# thermocouple_v0_1.net
KiCad netlist of a schematic drawn in EAGLE
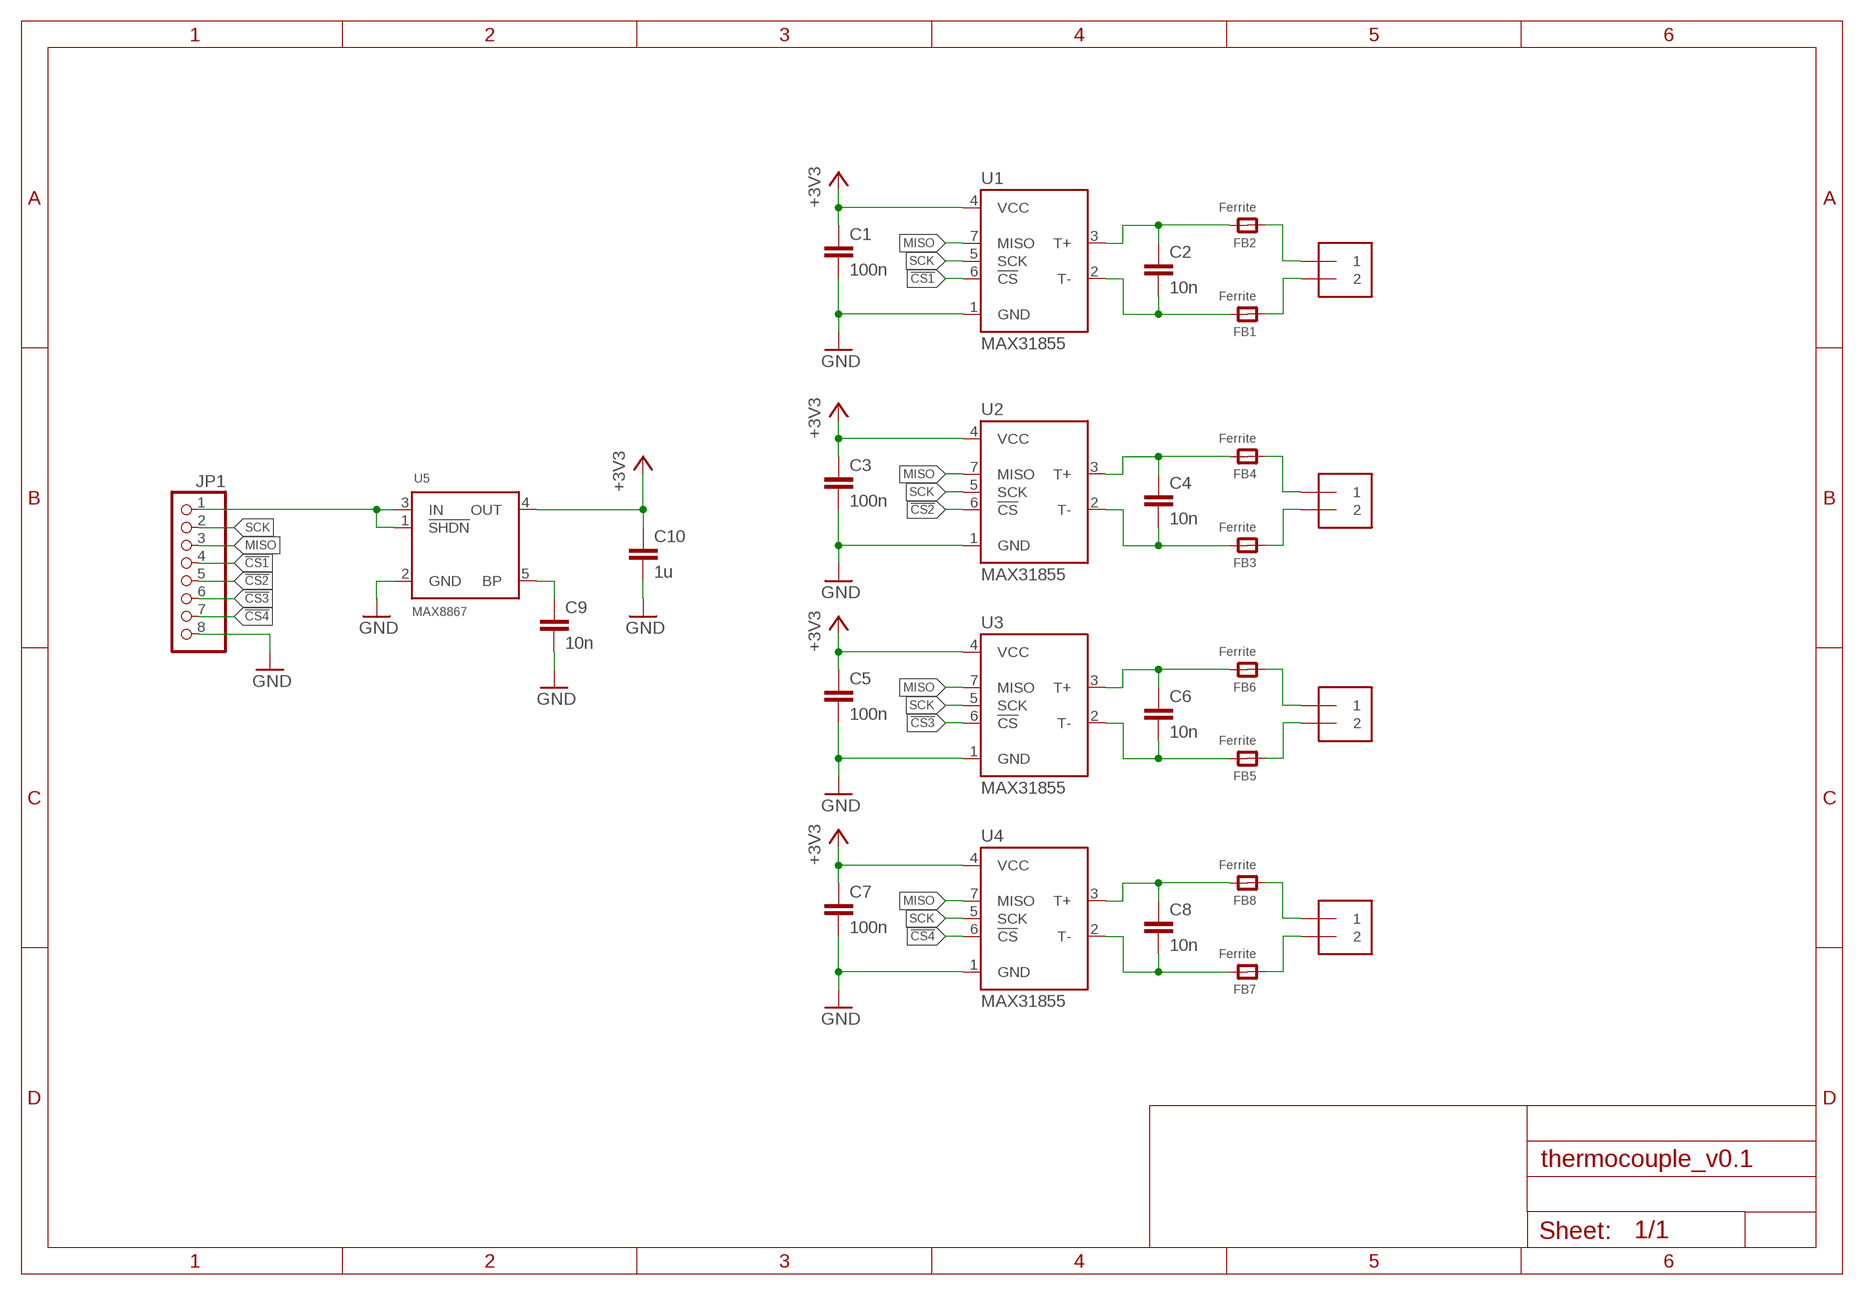
[diagram p0: schematic, sheet 1]

(export (version "E")
  (design (tool "Eeschema 10.0.6"))
  (components
    (comp (ref "C1")
      (value "100n")
      (footprint "eagle-import:C0603")
      (libsource (lib "eagle-import") (part "C-EUC0603"))
    )
    (comp (ref "C2")
      (value "10n")
      (footprint "eagle-import:C0603")
      (libsource (lib "eagle-import") (part "C-EUC0603"))
    )
    (comp (ref "C3")
      (value "100n")
      (footprint "eagle-import:C0603")
      (libsource (lib "eagle-import") (part "C-EUC0603"))
    )
    (comp (ref "C4")
      (value "10n")
      (footprint "eagle-import:C0603")
      (libsource (lib "eagle-import") (part "C-EUC0603"))
    )
    (comp (ref "C5")
      (value "100n")
      (footprint "eagle-import:C0603")
      (libsource (lib "eagle-import") (part "C-EUC0603"))
    )
    (comp (ref "C6")
      (value "10n")
      (footprint "eagle-import:C0603")
      (libsource (lib "eagle-import") (part "C-EUC0603"))
    )
    (comp (ref "C7")
      (value "100n")
      (footprint "eagle-import:C0603")
      (libsource (lib "eagle-import") (part "C-EUC0603"))
    )
    (comp (ref "C8")
      (value "10n")
      (footprint "eagle-import:C0603")
      (libsource (lib "eagle-import") (part "C-EUC0603"))
    )
    (comp (ref "C9")
      (value "10n")
      (footprint "eagle-import:C0603")
      (libsource (lib "eagle-import") (part "C-EUC0603"))
    )
    (comp (ref "C10")
      (value "1u")
      (footprint "eagle-import:C0603")
      (libsource (lib "eagle-import") (part "C-EUC0603"))
    )
    (comp (ref "FB1")
      (value "Ferrite")
      (footprint "eagle-import:_0805")
      (libsource (lib "eagle-import") (part "FERRITE_0805"))
    )
    (comp (ref "FB2")
      (value "Ferrite")
      (footprint "eagle-import:_0805")
      (libsource (lib "eagle-import") (part "FERRITE_0805"))
    )
    (comp (ref "FB3")
      (value "Ferrite")
      (footprint "eagle-import:_0805")
      (libsource (lib "eagle-import") (part "FERRITE_0805"))
    )
    (comp (ref "FB4")
      (value "Ferrite")
      (footprint "eagle-import:_0805")
      (libsource (lib "eagle-import") (part "FERRITE_0805"))
    )
    (comp (ref "FB5")
      (value "Ferrite")
      (footprint "eagle-import:_0805")
      (libsource (lib "eagle-import") (part "FERRITE_0805"))
    )
    (comp (ref "FB6")
      (value "Ferrite")
      (footprint "eagle-import:_0805")
      (libsource (lib "eagle-import") (part "FERRITE_0805"))
    )
    (comp (ref "FB7")
      (value "Ferrite")
      (footprint "eagle-import:_0805")
      (libsource (lib "eagle-import") (part "FERRITE_0805"))
    )
    (comp (ref "FB8")
      (value "Ferrite")
      (footprint "eagle-import:_0805")
      (libsource (lib "eagle-import") (part "FERRITE_0805"))
    )
    (comp (ref "J1")
      (value "1X2-3.5MM")
      (footprint "eagle-import:1X2-3.5MM")
      (libsource (lib "eagle-import") (part "1X2-3.5MM"))
    )
    (comp (ref "J2")
      (value "1X2-3.5MM")
      (footprint "eagle-import:1X2-3.5MM")
      (libsource (lib "eagle-import") (part "1X2-3.5MM"))
    )
    (comp (ref "J3")
      (value "1X2-3.5MM")
      (footprint "eagle-import:1X2-3.5MM")
      (libsource (lib "eagle-import") (part "1X2-3.5MM"))
    )
    (comp (ref "J4")
      (value "1X2-3.5MM")
      (footprint "eagle-import:1X2-3.5MM")
      (libsource (lib "eagle-import") (part "1X2-3.5MM"))
    )
    (comp (ref "JP1")
      (value "PINHD-1X8")
      (footprint "eagle-import:1X08")
      (libsource (lib "eagle-import") (part "PINHD-1X8"))
    )
    (comp (ref "U1")
      (value "MAX31855")
      (footprint "eagle-import:SO08")
      (libsource (lib "eagle-import") (part "MAX31855"))
    )
    (comp (ref "U2")
      (value "MAX31855")
      (footprint "eagle-import:SO08")
      (libsource (lib "eagle-import") (part "MAX31855"))
    )
    (comp (ref "U3")
      (value "MAX31855")
      (footprint "eagle-import:SO08")
      (libsource (lib "eagle-import") (part "MAX31855"))
    )
    (comp (ref "U4")
      (value "MAX31855")
      (footprint "eagle-import:SO08")
      (libsource (lib "eagle-import") (part "MAX31855"))
    )
    (comp (ref "U5")
      (value "MAX8867")
      (footprint "eagle-import:SOT23-5L")
      (libsource (lib "eagle-import") (part "MAX8867"))
    )
  )
  (nets
    (net (code "1") (name "+3V3") (class "Default")
      (node (ref "C1") (pin "1") (pinfunction "1_1") (pintype "passive"))
      (node (ref "C10") (pin "1") (pinfunction "1_1") (pintype "passive"))
      (node (ref "C3") (pin "1") (pinfunction "1_1") (pintype "passive"))
      (node (ref "C5") (pin "1") (pinfunction "1_1") (pintype "passive"))
      (node (ref "C7") (pin "1") (pinfunction "1_1") (pintype "passive"))
      (node (ref "U1") (pin "4") (pinfunction "VCC_4") (pintype "bidirectional"))
      (node (ref "U2") (pin "4") (pinfunction "VCC_4") (pintype "bidirectional"))
      (node (ref "U3") (pin "4") (pinfunction "VCC_4") (pintype "bidirectional"))
      (node (ref "U4") (pin "4") (pinfunction "VCC_4") (pintype "bidirectional"))
      (node (ref "U5") (pin "4") (pinfunction "OUT_4") (pintype "bidirectional"))
    )
    (net (code "2") (name "/~{CS1}") (class "Default")
      (node (ref "JP1") (pin "4") (pinfunction "4_4") (pintype "passive"))
      (node (ref "U1") (pin "6") (pinfunction "~{CS}_6") (pintype "bidirectional"))
    )
    (net (code "3") (name "/~{CS2}") (class "Default")
      (node (ref "JP1") (pin "5") (pinfunction "5_5") (pintype "passive"))
      (node (ref "U2") (pin "6") (pinfunction "~{CS}_6") (pintype "bidirectional"))
    )
    (net (code "4") (name "/~{CS3}") (class "Default")
      (node (ref "JP1") (pin "6") (pinfunction "6_6") (pintype "passive"))
      (node (ref "U3") (pin "6") (pinfunction "~{CS}_6") (pintype "bidirectional"))
    )
    (net (code "5") (name "/~{CS4}") (class "Default")
      (node (ref "JP1") (pin "7") (pinfunction "7_7") (pintype "passive"))
      (node (ref "U4") (pin "6") (pinfunction "~{CS}_6") (pintype "bidirectional"))
    )
    (net (code "6") (name "GND") (class "Default")
      (node (ref "C1") (pin "2") (pinfunction "2_2") (pintype "passive"))
      (node (ref "C10") (pin "2") (pinfunction "2_2") (pintype "passive"))
      (node (ref "C3") (pin "2") (pinfunction "2_2") (pintype "passive"))
      (node (ref "C5") (pin "2") (pinfunction "2_2") (pintype "passive"))
      (node (ref "C7") (pin "2") (pinfunction "2_2") (pintype "passive"))
      (node (ref "C9") (pin "2") (pinfunction "2_2") (pintype "passive"))
      (node (ref "JP1") (pin "8") (pinfunction "8_8") (pintype "passive"))
      (node (ref "U1") (pin "1") (pinfunction "GND_1") (pintype "bidirectional"))
      (node (ref "U2") (pin "1") (pinfunction "GND_1") (pintype "bidirectional"))
      (node (ref "U3") (pin "1") (pinfunction "GND_1") (pintype "bidirectional"))
      (node (ref "U4") (pin "1") (pinfunction "GND_1") (pintype "bidirectional"))
      (node (ref "U5") (pin "2") (pinfunction "GND_2") (pintype "bidirectional"))
    )
    (net (code "7") (name "MISO") (class "Default")
      (node (ref "JP1") (pin "3") (pinfunction "3_3") (pintype "passive"))
      (node (ref "U1") (pin "7") (pinfunction "MISO_7") (pintype "bidirectional"))
      (node (ref "U2") (pin "7") (pinfunction "MISO_7") (pintype "bidirectional"))
      (node (ref "U3") (pin "7") (pinfunction "MISO_7") (pintype "bidirectional"))
      (node (ref "U4") (pin "7") (pinfunction "MISO_7") (pintype "bidirectional"))
    )
    (net (code "8") (name "Net-(FB1-P$1)") (class "Default")
      (node (ref "FB1") (pin "1") (pinfunction "P$1_1") (pintype "passive"))
      (node (ref "J1") (pin "2") (pinfunction "2_2") (pintype "passive"))
    )
    (net (code "9") (name "Net-(FB1-P$2)") (class "Default")
      (node (ref "C2") (pin "2") (pinfunction "2_2") (pintype "passive"))
      (node (ref "FB1") (pin "2") (pinfunction "P$2_2") (pintype "passive"))
      (node (ref "U1") (pin "2") (pinfunction "T-_2") (pintype "bidirectional"))
    )
    (net (code "10") (name "Net-(FB2-P$1)") (class "Default")
      (node (ref "FB2") (pin "1") (pinfunction "P$1_1") (pintype "passive"))
      (node (ref "J1") (pin "1") (pinfunction "1_1") (pintype "passive"))
    )
    (net (code "11") (name "Net-(FB2-P$2)") (class "Default")
      (node (ref "C2") (pin "1") (pinfunction "1_1") (pintype "passive"))
      (node (ref "FB2") (pin "2") (pinfunction "P$2_2") (pintype "passive"))
      (node (ref "U1") (pin "3") (pinfunction "T+_3") (pintype "bidirectional"))
    )
    (net (code "12") (name "Net-(FB3-P$1)") (class "Default")
      (node (ref "FB3") (pin "1") (pinfunction "P$1_1") (pintype "passive"))
      (node (ref "J2") (pin "2") (pinfunction "2_2") (pintype "passive"))
    )
    (net (code "13") (name "Net-(FB3-P$2)") (class "Default")
      (node (ref "C4") (pin "2") (pinfunction "2_2") (pintype "passive"))
      (node (ref "FB3") (pin "2") (pinfunction "P$2_2") (pintype "passive"))
      (node (ref "U2") (pin "2") (pinfunction "T-_2") (pintype "bidirectional"))
    )
    (net (code "14") (name "Net-(FB4-P$1)") (class "Default")
      (node (ref "FB4") (pin "1") (pinfunction "P$1_1") (pintype "passive"))
      (node (ref "J2") (pin "1") (pinfunction "1_1") (pintype "passive"))
    )
    (net (code "15") (name "Net-(FB4-P$2)") (class "Default")
      (node (ref "C4") (pin "1") (pinfunction "1_1") (pintype "passive"))
      (node (ref "FB4") (pin "2") (pinfunction "P$2_2") (pintype "passive"))
      (node (ref "U2") (pin "3") (pinfunction "T+_3") (pintype "bidirectional"))
    )
    (net (code "16") (name "Net-(FB5-P$1)") (class "Default")
      (node (ref "FB5") (pin "1") (pinfunction "P$1_1") (pintype "passive"))
      (node (ref "J3") (pin "2") (pinfunction "2_2") (pintype "passive"))
    )
    (net (code "17") (name "Net-(FB5-P$2)") (class "Default")
      (node (ref "C6") (pin "2") (pinfunction "2_2") (pintype "passive"))
      (node (ref "FB5") (pin "2") (pinfunction "P$2_2") (pintype "passive"))
      (node (ref "U3") (pin "2") (pinfunction "T-_2") (pintype "bidirectional"))
    )
    (net (code "18") (name "Net-(FB6-P$1)") (class "Default")
      (node (ref "FB6") (pin "1") (pinfunction "P$1_1") (pintype "passive"))
      (node (ref "J3") (pin "1") (pinfunction "1_1") (pintype "passive"))
    )
    (net (code "19") (name "Net-(FB6-P$2)") (class "Default")
      (node (ref "C6") (pin "1") (pinfunction "1_1") (pintype "passive"))
      (node (ref "FB6") (pin "2") (pinfunction "P$2_2") (pintype "passive"))
      (node (ref "U3") (pin "3") (pinfunction "T+_3") (pintype "bidirectional"))
    )
    (net (code "20") (name "Net-(FB7-P$1)") (class "Default")
      (node (ref "FB7") (pin "1") (pinfunction "P$1_1") (pintype "passive"))
      (node (ref "J4") (pin "2") (pinfunction "2_2") (pintype "passive"))
    )
    (net (code "21") (name "Net-(FB7-P$2)") (class "Default")
      (node (ref "C8") (pin "2") (pinfunction "2_2") (pintype "passive"))
      (node (ref "FB7") (pin "2") (pinfunction "P$2_2") (pintype "passive"))
      (node (ref "U4") (pin "2") (pinfunction "T-_2") (pintype "bidirectional"))
    )
    (net (code "22") (name "Net-(FB8-P$1)") (class "Default")
      (node (ref "FB8") (pin "1") (pinfunction "P$1_1") (pintype "passive"))
      (node (ref "J4") (pin "1") (pinfunction "1_1") (pintype "passive"))
    )
    (net (code "23") (name "Net-(FB8-P$2)") (class "Default")
      (node (ref "C8") (pin "1") (pinfunction "1_1") (pintype "passive"))
      (node (ref "FB8") (pin "2") (pinfunction "P$2_2") (pintype "passive"))
      (node (ref "U4") (pin "3") (pinfunction "T+_3") (pintype "bidirectional"))
    )
    (net (code "24") (name "Net-(U5-BP)") (class "Default")
      (node (ref "C9") (pin "1") (pinfunction "1_1") (pintype "passive"))
      (node (ref "U5") (pin "5") (pinfunction "BP_5") (pintype "bidirectional"))
    )
    (net (code "25") (name "Net-(U5-IN)") (class "Default")
      (node (ref "JP1") (pin "1") (pinfunction "1_1") (pintype "passive"))
      (node (ref "U5") (pin "1") (pinfunction "~{SHDN}_1") (pintype "bidirectional"))
      (node (ref "U5") (pin "3") (pinfunction "IN_3") (pintype "bidirectional"))
    )
    (net (code "26") (name "SCK") (class "Default")
      (node (ref "JP1") (pin "2") (pinfunction "2_2") (pintype "passive"))
      (node (ref "U1") (pin "5") (pinfunction "SCK_5") (pintype "bidirectional"))
      (node (ref "U2") (pin "5") (pinfunction "SCK_5") (pintype "bidirectional"))
      (node (ref "U3") (pin "5") (pinfunction "SCK_5") (pintype "bidirectional"))
      (node (ref "U4") (pin "5") (pinfunction "SCK_5") (pintype "bidirectional"))
    )
  )
)
